# charging.net
KiCad netlist of a schematic drawn in EAGLE
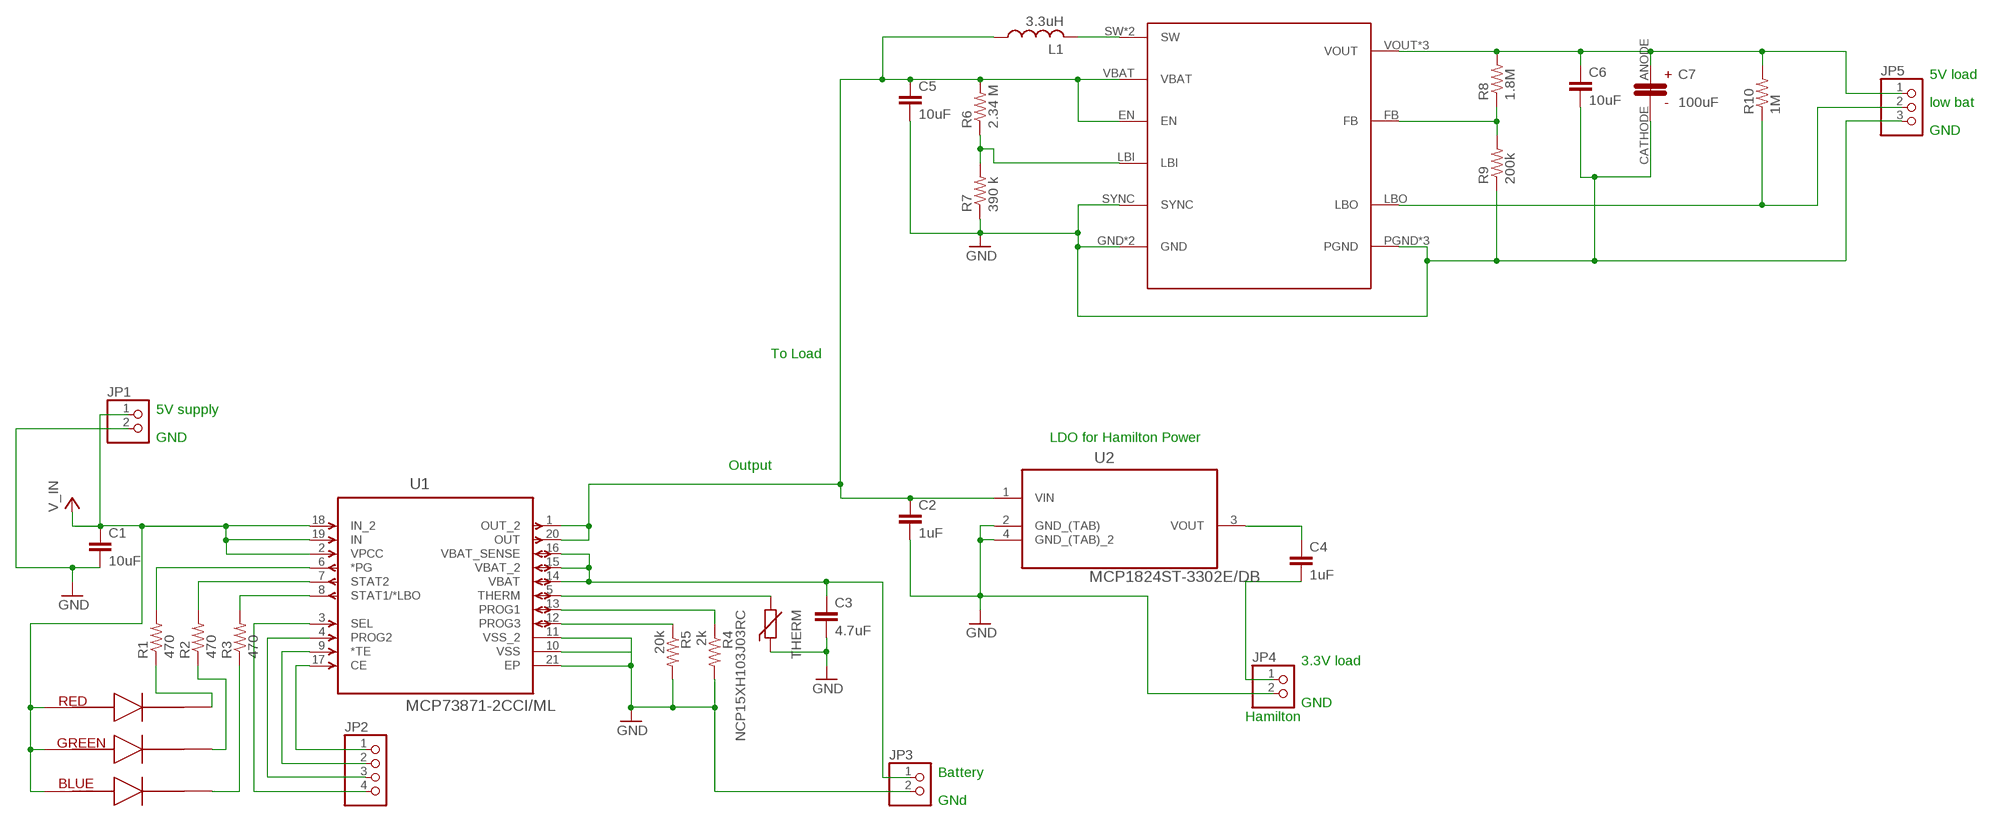
[diagram p0: schematic, sheet 1]

(export (version "E")
  (design (tool "Eeschema 10.0.6"))
  (components
    (comp (ref "C1")
      (value "10uF")
      (footprint "eagle-import:C0805")
      (libsource (lib "eagle-import") (part "C-EUC0805"))
    )
    (comp (ref "C2")
      (value "1uF")
      (footprint "eagle-import:C0603K")
      (libsource (lib "eagle-import") (part "C-EUC0603K"))
    )
    (comp (ref "C3")
      (value "4.7uF")
      (footprint "eagle-import:C0805")
      (libsource (lib "eagle-import") (part "C-EUC0805"))
    )
    (comp (ref "C4")
      (value "1uF")
      (footprint "eagle-import:C0603K")
      (libsource (lib "eagle-import") (part "C-EUC0603K"))
    )
    (comp (ref "C5")
      (value "10uF")
      (footprint "eagle-import:C0603K")
      (libsource (lib "eagle-import") (part "C-EUC0603K"))
    )
    (comp (ref "C6")
      (value "10uF")
      (footprint "eagle-import:C0603K")
      (libsource (lib "eagle-import") (part "C-EUC0603K"))
    )
    (comp (ref "C7")
      (value "100uF")
      (footprint "eagle-import:6032")
      (libsource (lib "eagle-import") (part "T491C686K010AT"))
    )
    (comp (ref "JP1")
      (value "PINHD-1X2")
      (footprint "eagle-import:1X02")
      (libsource (lib "eagle-import") (part "PINHD-1X2"))
    )
    (comp (ref "JP2")
      (value "PINHD-1X4")
      (footprint "eagle-import:1X04")
      (libsource (lib "eagle-import") (part "PINHD-1X4"))
    )
    (comp (ref "JP3")
      (value "PINHD-1X2")
      (footprint "eagle-import:1X02")
      (libsource (lib "eagle-import") (part "PINHD-1X2"))
    )
    (comp (ref "JP4")
      (value "PINHD-1X2")
      (footprint "eagle-import:1X02")
      (libsource (lib "eagle-import") (part "PINHD-1X2"))
    )
    (comp (ref "JP5")
      (value "PINHD-1X3")
      (footprint "eagle-import:1X03")
      (libsource (lib "eagle-import") (part "PINHD-1X3"))
    )
    (comp (ref "L1")
      (value "3.3uH")
      (footprint "eagle-import:2-SMD")
      (libsource (lib "eagle-import") (part "L-US"))
    )
    (comp (ref "R1")
      (value "470")
      (footprint "eagle-import:R0805")
      (libsource (lib "eagle-import") (part "R-US_R0805"))
    )
    (comp (ref "R2")
      (value "470")
      (footprint "eagle-import:R0805")
      (libsource (lib "eagle-import") (part "R-US_R0805"))
    )
    (comp (ref "R3")
      (value "470")
      (footprint "eagle-import:R0805")
      (libsource (lib "eagle-import") (part "R-US_R0805"))
    )
    (comp (ref "R4")
      (value "2k")
      (footprint "eagle-import:R0805")
      (libsource (lib "eagle-import") (part "R-US_R0805"))
    )
    (comp (ref "R5")
      (value "20k")
      (footprint "eagle-import:R0805")
      (libsource (lib "eagle-import") (part "R-US_R0805"))
    )
    (comp (ref "R6")
      (value "2.34 M")
      (footprint "eagle-import:R0603")
      (libsource (lib "eagle-import") (part "R-US_R0603"))
    )
    (comp (ref "R7")
      (value "390 k")
      (footprint "eagle-import:R0603")
      (libsource (lib "eagle-import") (part "R-US_R0603"))
    )
    (comp (ref "R8")
      (value "1.8M")
      (footprint "eagle-import:R0603")
      (libsource (lib "eagle-import") (part "R-US_R0603"))
    )
    (comp (ref "R9")
      (value "200k")
      (footprint "eagle-import:R0603")
      (libsource (lib "eagle-import") (part "R-US_R0603"))
    )
    (comp (ref "R10")
      (value "1M")
      (footprint "eagle-import:R0603")
      (libsource (lib "eagle-import") (part "R-US_R0603"))
    )
    (comp (ref "THERM")
      (value "NCP15XH103J03RC")
      (footprint "eagle-import:CT_CN0402")
      (libsource (lib "eagle-import") (part "NCP15XH103J03RC"))
    )
    (comp (ref "U$1")
      (value "CLP6C-FKB")
      (footprint "eagle-import:CREE_PLCC6_3-IN-1_SMD_LED_CLP6C-FKB")
      (libsource (lib "eagle-import") (part "CLP6C-FKB"))
    )
    (comp (ref "U$2")
      (value "TPS61090")
      (footprint "eagle-import:QFN-16")
      (libsource (lib "eagle-import") (part "TPS61090"))
    )
    (comp (ref "U1")
      (value "MCP73871-2CCI/ML")
      (footprint "eagle-import:QFN50P400X400X100-21N")
      (libsource (lib "eagle-import") (part "MCP73871-2CCI/ML"))
    )
    (comp (ref "U2")
      (value "MCP1824ST-3302E/DB")
      (footprint "eagle-import:SOT230P700X180-4N")
      (libsource (lib "eagle-import") (part "MCP1824ST-3302E/DB"))
    )
  )
  (nets
    (net (code "1") (name "GND") (class "Default")
      (node (ref "C1") (pin "2") (pinfunction "2_2") (pintype "passive"))
      (node (ref "C2") (pin "2") (pinfunction "2_2") (pintype "passive"))
      (node (ref "C3") (pin "2") (pinfunction "2_2") (pintype "passive"))
      (node (ref "C5") (pin "2") (pinfunction "2_2") (pintype "passive"))
      (node (ref "C6") (pin "2") (pinfunction "2_2") (pintype "passive"))
      (node (ref "C7") (pin "CATHODE") (pinfunction "CATHODE_CATHODE") (pintype "bidirectional"))
      (node (ref "JP1") (pin "2") (pinfunction "2_2") (pintype "passive"))
      (node (ref "JP3") (pin "2") (pinfunction "2_2") (pintype "passive"))
      (node (ref "JP4") (pin "2") (pinfunction "2_2") (pintype "passive"))
      (node (ref "JP5") (pin "3") (pinfunction "3_3") (pintype "passive"))
      (node (ref "R4") (pin "2") (pinfunction "2_2") (pintype "passive"))
      (node (ref "R5") (pin "2") (pinfunction "2_2") (pintype "passive"))
      (node (ref "R7") (pin "1") (pinfunction "1_1") (pintype "passive"))
      (node (ref "R9") (pin "1") (pinfunction "1_1") (pintype "passive"))
      (node (ref "THERM") (pin "1") (pinfunction "1_1") (pintype "passive"))
      (node (ref "U$2") (pin "GND") (pinfunction "GND_GND") (pintype "bidirectional"))
      (node (ref "U$2") (pin "P$17") (pinfunction "GND_P$17") (pintype "bidirectional"))
      (node (ref "U$2") (pin "PGND") (pinfunction "PGND_PGND") (pintype "bidirectional"))
      (node (ref "U$2") (pin "PGND_2") (pinfunction "PGND_PGND_2") (pintype "bidirectional"))
      (node (ref "U$2") (pin "PGND_3") (pinfunction "PGND_PGND_3") (pintype "bidirectional"))
      (node (ref "U$2") (pin "SYNC") (pinfunction "SYNC_SYNC") (pintype "bidirectional"))
      (node (ref "U1") (pin "10") (pinfunction "VSS_10") (pintype "power_in"))
      (node (ref "U1") (pin "11") (pinfunction "VSS_2_11") (pintype "power_in"))
      (node (ref "U1") (pin "21") (pinfunction "EP_21") (pintype "passive"))
      (node (ref "U2") (pin "2") (pinfunction "GND_(TAB)_2") (pintype "passive"))
      (node (ref "U2") (pin "4") (pinfunction "GND_(TAB)_2_4") (pintype "passive"))
    )
    (net (code "2") (name "Net-(C4-Pad2)") (class "Default")
      (node (ref "C4") (pin "2") (pinfunction "2_2") (pintype "passive"))
      (node (ref "JP4") (pin "1") (pinfunction "1_1") (pintype "passive"))
    )
    (net (code "3") (name "Net-(C6-Pad1)") (class "Default")
      (node (ref "C6") (pin "1") (pinfunction "1_1") (pintype "passive"))
      (node (ref "C7") (pin "ANODE") (pinfunction "ANODE_ANODE") (pintype "bidirectional"))
      (node (ref "JP5") (pin "1") (pinfunction "1_1") (pintype "passive"))
      (node (ref "R10") (pin "2") (pinfunction "2_2") (pintype "passive"))
      (node (ref "R8") (pin "2") (pinfunction "2_2") (pintype "passive"))
      (node (ref "U$2") (pin "VOUT") (pinfunction "VOUT_VOUT") (pintype "bidirectional"))
      (node (ref "U$2") (pin "VOUT_2") (pinfunction "VOUT_VOUT_2") (pintype "bidirectional"))
      (node (ref "U$2") (pin "VOUT_3") (pinfunction "VOUT_VOUT_3") (pintype "bidirectional"))
    )
    (net (code "4") (name "Net-(JP5-Pad2)") (class "Default")
      (node (ref "JP5") (pin "2") (pinfunction "2_2") (pintype "passive"))
      (node (ref "R10") (pin "1") (pinfunction "1_1") (pintype "passive"))
      (node (ref "U$2") (pin "LBO") (pinfunction "LBO_LBO") (pintype "bidirectional"))
    )
    (net (code "5") (name "Net-(L1-1)") (class "Default")
      (node (ref "C2") (pin "1") (pinfunction "1_1") (pintype "passive"))
      (node (ref "C5") (pin "1") (pinfunction "1_1") (pintype "passive"))
      (node (ref "L1") (pin "P$1") (pinfunction "1_P$1") (pintype "passive"))
      (node (ref "R6") (pin "2") (pinfunction "2_2") (pintype "passive"))
      (node (ref "U$2") (pin "EN") (pinfunction "EN_EN") (pintype "bidirectional"))
      (node (ref "U$2") (pin "VBAT") (pinfunction "VBAT_VBAT") (pintype "bidirectional"))
      (node (ref "U1") (pin "1") (pinfunction "OUT_2_1") (pintype "output"))
      (node (ref "U1") (pin "20") (pinfunction "OUT_20") (pintype "output"))
      (node (ref "U2") (pin "1") (pinfunction "VIN_1") (pintype "input"))
    )
    (net (code "6") (name "Net-(L1-2)") (class "Default")
      (node (ref "L1") (pin "P$2") (pinfunction "2_P$2") (pintype "passive"))
      (node (ref "U$2") (pin "SW") (pinfunction "SW_SW") (pintype "bidirectional"))
      (node (ref "U$2") (pin "SW_2") (pinfunction "SW_SW_2") (pintype "bidirectional"))
    )
    (net (code "7") (name "Net-(R1-Pad1)") (class "Default")
      (node (ref "R1") (pin "1") (pinfunction "1_1") (pintype "passive"))
      (node (ref "U$1") (pin "RED_CATHODE") (pinfunction "RED_CATHODE_RED_CATHODE") (pintype "bidirectional"))
    )
    (net (code "8") (name "Net-(R2-Pad1)") (class "Default")
      (node (ref "R2") (pin "1") (pinfunction "1_1") (pintype "passive"))
      (node (ref "U$1") (pin "GREEN_CATHODE") (pinfunction "GREEN_CATHODE_GREEN_CATHODE") (pintype "bidirectional"))
    )
    (net (code "9") (name "Net-(R3-Pad1)") (class "Default")
      (node (ref "R3") (pin "1") (pinfunction "1_1") (pintype "passive"))
      (node (ref "U$1") (pin "BLUE_CATHODE") (pinfunction "BLUE_CATHODE_BLUE_CATHODE") (pintype "bidirectional"))
    )
    (net (code "10") (name "Net-(R6-Pad1)") (class "Default")
      (node (ref "R6") (pin "1") (pinfunction "1_1") (pintype "passive"))
      (node (ref "R7") (pin "2") (pinfunction "2_2") (pintype "passive"))
      (node (ref "U$2") (pin "LBI") (pinfunction "LBI_LBI") (pintype "bidirectional"))
    )
    (net (code "11") (name "Net-(R8-Pad1)") (class "Default")
      (node (ref "R8") (pin "1") (pinfunction "1_1") (pintype "passive"))
      (node (ref "R9") (pin "2") (pinfunction "2_2") (pintype "passive"))
      (node (ref "U$2") (pin "FB") (pinfunction "FB_FB") (pintype "bidirectional"))
    )
    (net (code "12") (name "Net-(U1-*PG)") (class "Default")
      (node (ref "R1") (pin "2") (pinfunction "2_2") (pintype "passive"))
      (node (ref "U1") (pin "6") (pinfunction "*PG_6") (pintype "output"))
    )
    (net (code "13") (name "Net-(U1-*TE)") (class "Default")
      (node (ref "JP2") (pin "2") (pinfunction "2_2") (pintype "passive"))
      (node (ref "U1") (pin "9") (pinfunction "*TE_9") (pintype "input"))
    )
    (net (code "14") (name "Net-(U1-CE)") (class "Default")
      (node (ref "JP2") (pin "1") (pinfunction "1_1") (pintype "passive"))
      (node (ref "U1") (pin "17") (pinfunction "CE_17") (pintype "input"))
    )
    (net (code "15") (name "Net-(U1-PROG1)") (class "Default")
      (node (ref "R4") (pin "1") (pinfunction "1_1") (pintype "passive"))
      (node (ref "U1") (pin "13") (pinfunction "PROG1_13") (pintype "bidirectional"))
    )
    (net (code "16") (name "Net-(U1-PROG2)") (class "Default")
      (node (ref "JP2") (pin "3") (pinfunction "3_3") (pintype "passive"))
      (node (ref "U1") (pin "4") (pinfunction "PROG2_4") (pintype "input"))
    )
    (net (code "17") (name "Net-(U1-PROG3)") (class "Default")
      (node (ref "R5") (pin "1") (pinfunction "1_1") (pintype "passive"))
      (node (ref "U1") (pin "12") (pinfunction "PROG3_12") (pintype "bidirectional"))
    )
    (net (code "18") (name "Net-(U1-SEL)") (class "Default")
      (node (ref "JP2") (pin "4") (pinfunction "4_4") (pintype "passive"))
      (node (ref "U1") (pin "3") (pinfunction "SEL_3") (pintype "input"))
    )
    (net (code "19") (name "Net-(U1-STAT1{slash}*LBO)") (class "Default")
      (node (ref "R3") (pin "2") (pinfunction "2_2") (pintype "passive"))
      (node (ref "U1") (pin "8") (pinfunction "STAT1/*LBO_8") (pintype "output"))
    )
    (net (code "20") (name "Net-(U1-STAT2)") (class "Default")
      (node (ref "R2") (pin "2") (pinfunction "2_2") (pintype "passive"))
      (node (ref "U1") (pin "7") (pinfunction "STAT2_7") (pintype "output"))
    )
    (net (code "21") (name "Net-(U1-THERM)") (class "Default")
      (node (ref "THERM") (pin "2") (pinfunction "2_2") (pintype "passive"))
      (node (ref "U1") (pin "5") (pinfunction "THERM_5") (pintype "bidirectional"))
    )
    (net (code "22") (name "Net-(U1-VBAT)") (class "Default")
      (node (ref "C3") (pin "1") (pinfunction "1_1") (pintype "passive"))
      (node (ref "JP3") (pin "1") (pinfunction "1_1") (pintype "passive"))
      (node (ref "U1") (pin "14") (pinfunction "VBAT_14") (pintype "bidirectional"))
      (node (ref "U1") (pin "15") (pinfunction "VBAT_2_15") (pintype "bidirectional"))
      (node (ref "U1") (pin "16") (pinfunction "VBAT_SENSE_16") (pintype "bidirectional"))
    )
    (net (code "23") (name "Net-(U2-VOUT)") (class "Default")
      (node (ref "C4") (pin "1") (pinfunction "1_1") (pintype "passive"))
      (node (ref "U2") (pin "3") (pinfunction "VOUT_3") (pintype "output"))
    )
    (net (code "24") (name "V_IN") (class "Default")
      (node (ref "C1") (pin "1") (pinfunction "1_1") (pintype "passive"))
      (node (ref "JP1") (pin "1") (pinfunction "1_1") (pintype "passive"))
      (node (ref "U$1") (pin "BLUE_ANODE") (pinfunction "BLUE_ANODE_BLUE_ANODE") (pintype "bidirectional"))
      (node (ref "U$1") (pin "GREEN_ANODE") (pinfunction "GREEN_ANODE_GREEN_ANODE") (pintype "bidirectional"))
      (node (ref "U$1") (pin "RED_ANODE") (pinfunction "RED_ANODE_RED_ANODE") (pintype "bidirectional"))
      (node (ref "U1") (pin "18") (pinfunction "IN_2_18") (pintype "input"))
      (node (ref "U1") (pin "19") (pinfunction "IN_19") (pintype "input"))
      (node (ref "U1") (pin "2") (pinfunction "VPCC_2") (pintype "input"))
    )
  )
)
